# Sheet_1_2025-02-08.net
KiCad netlist of a schematic drawn in Altium Designer
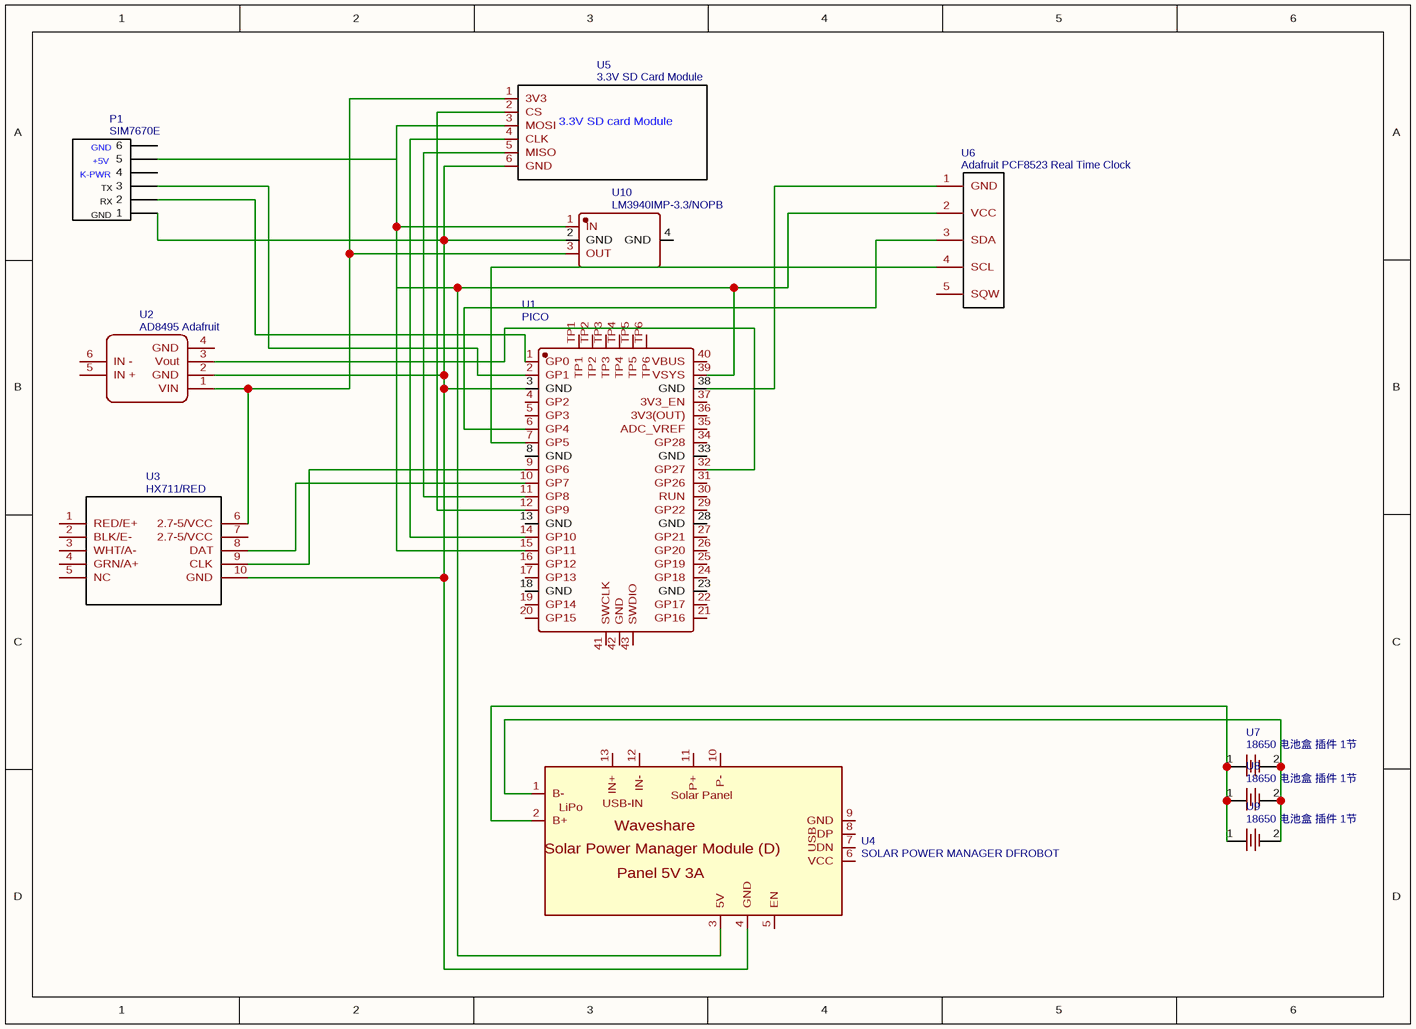
[diagram p0: Sheet_1_2025-02-08.schdoc]

(export (version "E")
  (design (tool "Eeschema 10.0.6"))
  (components
    (comp (ref "P1")
      (value "SIM7670E")
      (fields
        (field (name "MANUFACTURER") "LCSC")
        (field (name "MANUFACTURER PART") "Header-Male-2.54_1x6")
        (field (name "CONTRIBUTOR") "mrilic66")
      )
      (libsource (lib "altium-import") (part "root_2_SIM7670E_"))
    )
    (comp (ref "U1")
      (value "PICO")
      (fields (field (name "MANUFACTURER") "Raspberry Pi(树莓派)") (field (name "CONTRIBUTOR") "lcsc"))
      (libsource (lib "altium-import") (part "root_0_PICO_"))
    )
    (comp (ref "U2")
      (value "AD8495 Adafruit")
      (fields
        (field (name "MANUFACTURER") "Adafruit")
        (field (name "MANUFACTURER PART") "1778")
        (field (name "CONTRIBUTOR") "ralph.v.montfort")
      )
      (libsource (lib "altium-import") (part "root_2_AD8495 Adafruit_"))
    )
    (comp (ref "U3")
      (value "HX711/RED")
      (fields (field (name "CONTRIBUTOR") "lwmd92"))
      (libsource (lib "altium-import") (part "root_0_HX711/RED_"))
    )
    (comp (ref "U4")
      (value "SOLAR POWER MANAGER DFROBOT")
      (fields (field (name "MANUFACTURER") "Sunflower") (field (name "CONTRIBUTOR") "ManarAlkammessy1"))
      (libsource (lib "altium-import") (part "root_0_SOLAR POWER MANAGER DFROBOT_"))
    )
    (comp (ref "U5")
      (value "3.3V SD Card Module")
      (fields (field (name "CONTRIBUTOR") "sumeda91"))
      (libsource (lib "altium-import") (part "root_0_3.3V SD Card Module_"))
    )
    (comp (ref "U6")
      (value "Adafruit PCF8523 Real Time Clock")
      (fields (field (name "CONTRIBUTOR") "Israrengineering"))
      (libsource (lib "altium-import") (part "root_2_Adafruit PCF8523 Real Time Clock_"))
    )
    (comp (ref "U7")
      (value "18650 电池盒 插件 1节")
      (fields (field (name "CONTRIBUTOR") "LCSC"))
      (libsource (lib "altium-import") (part "root_0_18650 电池盒 插件 1节_"))
    )
    (comp (ref "U8")
      (value "18650 电池盒 插件 1节")
      (fields (field (name "CONTRIBUTOR") "LCSC"))
      (libsource (lib "altium-import") (part "root_0_18650 电池盒 插件 1节_"))
    )
    (comp (ref "U9")
      (value "18650 电池盒 插件 1节")
      (fields (field (name "CONTRIBUTOR") "LCSC"))
      (libsource (lib "altium-import") (part "root_0_18650 电池盒 插件 1节_"))
    )
    (comp (ref "U10")
      (value "LM3940IMP-3.3/NOPB")
      (fields (field (name "MANUFACTURER") "TI(德州仪器)") (field (name "CONTRIBUTOR") "LCSC"))
      (libsource (lib "altium-import") (part "root_0_LM3940IMP-3.3/NOPB_"))
    )
  )
  (nets
    (net (code "1") (name "Net-(U1-GP0)") (class "Default")
      (node (ref "P1") (pin "2") (pinfunction "2_2") (pintype "passive"))
      (node (ref "U1") (pin "1") (pinfunction "GP0_1") (pintype "passive"))
    )
    (net (code "2") (name "Net-(U1-GP1)") (class "Default")
      (node (ref "P1") (pin "3") (pinfunction "3_3") (pintype "passive"))
      (node (ref "U1") (pin "2") (pinfunction "GP1_2") (pintype "passive"))
    )
    (net (code "3") (name "Net-(U1-GP4)") (class "Default")
      (node (ref "U1") (pin "6") (pinfunction "GP4_6") (pintype "passive"))
      (node (ref "U6") (pin "3") (pinfunction "SDA_3") (pintype "passive"))
    )
    (net (code "4") (name "Net-(U1-GP5)") (class "Default")
      (node (ref "U1") (pin "7") (pinfunction "GP5_7") (pintype "passive"))
      (node (ref "U6") (pin "4") (pinfunction "SCL_4") (pintype "passive"))
    )
    (net (code "5") (name "Net-(U1-GP6)") (class "Default")
      (node (ref "U1") (pin "9") (pinfunction "GP6_9") (pintype "passive"))
      (node (ref "U3") (pin "9") (pinfunction "CLK_9") (pintype "passive"))
    )
    (net (code "6") (name "Net-(U1-GP7)") (class "Default")
      (node (ref "U1") (pin "10") (pinfunction "GP7_10") (pintype "passive"))
      (node (ref "U3") (pin "8") (pinfunction "DAT_8") (pintype "passive"))
    )
    (net (code "7") (name "Net-(U1-GP8)") (class "Default")
      (node (ref "U1") (pin "11") (pinfunction "GP8_11") (pintype "passive"))
      (node (ref "U5") (pin "5") (pinfunction "MISO_5") (pintype "passive"))
    )
    (net (code "8") (name "Net-(U1-GP9)") (class "Default")
      (node (ref "U1") (pin "12") (pinfunction "GP9_12") (pintype "passive"))
      (node (ref "U5") (pin "2") (pinfunction "CS_2") (pintype "passive"))
    )
    (net (code "9") (name "Net-(U1-GP10)") (class "Default")
      (node (ref "U1") (pin "14") (pinfunction "GP10_14") (pintype "passive"))
      (node (ref "U5") (pin "4") (pinfunction "CLK_4") (pintype "passive"))
    )
    (net (code "10") (name "Net-(U1-GP11)") (class "Default")
      (node (ref "P1") (pin "5") (pinfunction "5_5") (pintype "passive"))
      (node (ref "U1") (pin "15") (pinfunction "GP11_15") (pintype "passive"))
      (node (ref "U1") (pin "39") (pinfunction "VSYS_39") (pintype "passive"))
      (node (ref "U10") (pin "1") (pinfunction "IN_1") (pintype "passive"))
      (node (ref "U4") (pin "3") (pinfunction "5V_3") (pintype "passive"))
      (node (ref "U5") (pin "3") (pinfunction "MOSI_3") (pintype "passive"))
      (node (ref "U6") (pin "2") (pinfunction "VCC_2") (pintype "passive"))
    )
    (net (code "11") (name "Net-(U1-GP27)") (class "Default")
      (node (ref "U1") (pin "32") (pinfunction "GP27_32") (pintype "passive"))
      (node (ref "U2") (pin "3") (pinfunction "Vout_3") (pintype "passive"))
    )
    (net (code "12") (name "Net-(U3-GND)") (class "Default")
      (node (ref "P1") (pin "1") (pinfunction "1_1") (pintype "passive"))
      (node (ref "U1") (pin "3") (pinfunction "GND_3") (pintype "passive"))
      (node (ref "U10") (pin "2") (pinfunction "GND_2") (pintype "passive"))
      (node (ref "U2") (pin "2") (pinfunction "GND_2") (pintype "passive"))
      (node (ref "U3") (pin "10") (pinfunction "GND_10") (pintype "passive"))
      (node (ref "U4") (pin "4") (pinfunction "GND_4") (pintype "passive"))
      (node (ref "U5") (pin "6") (pinfunction "GND_6") (pintype "passive"))
    )
    (net (code "13") (name "Net-(U4-B+)") (class "Default")
      (node (ref "U4") (pin "2") (pinfunction "B+_2") (pintype "passive"))
      (node (ref "U7") (pin "1") (pinfunction "1_1") (pintype "passive"))
      (node (ref "U8") (pin "1") (pinfunction "1_1") (pintype "passive"))
      (node (ref "U9") (pin "1") (pinfunction "1_1") (pintype "passive"))
    )
    (net (code "14") (name "Net-(U4-B-)") (class "Default")
      (node (ref "U4") (pin "1") (pinfunction "B-_1") (pintype "passive"))
      (node (ref "U7") (pin "2") (pinfunction "2_2") (pintype "passive"))
      (node (ref "U8") (pin "2") (pinfunction "2_2") (pintype "passive"))
      (node (ref "U9") (pin "2") (pinfunction "2_2") (pintype "passive"))
    )
    (net (code "15") (name "Net-(U6-GND)") (class "Default")
      (node (ref "U1") (pin "38") (pinfunction "GND_38") (pintype "passive"))
      (node (ref "U6") (pin "1") (pinfunction "GND_1") (pintype "passive"))
    )
    (net (code "16") (name "Net-(U10-OUT)") (class "Default")
      (node (ref "U10") (pin "3") (pinfunction "OUT_3") (pintype "passive"))
      (node (ref "U2") (pin "1") (pinfunction "VIN_1") (pintype "passive"))
      (node (ref "U3") (pin "6") (pinfunction "2.7-5/VCC_6") (pintype "passive"))
      (node (ref "U5") (pin "1") (pinfunction "3V3_1") (pintype "passive"))
    )
    (net (code "17") (name "unconnected-(P1-Pad4)") (class "Default")
      (node (ref "P1") (pin "4") (pinfunction "4_4") (pintype "passive"))
    )
    (net (code "18") (name "unconnected-(P1-Pad6)") (class "Default")
      (node (ref "P1") (pin "6") (pinfunction "6_6") (pintype "passive"))
    )
    (net (code "19") (name "unconnected-(U1-3V3(OUT)-Pad36)") (class "Default")
      (node (ref "U1") (pin "36") (pinfunction "3V3(OUT)_36") (pintype "passive"))
    )
    (net (code "20") (name "unconnected-(U1-3V3_EN-Pad37)") (class "Default")
      (node (ref "U1") (pin "37") (pinfunction "3V3_EN_37") (pintype "passive"))
    )
    (net (code "21") (name "unconnected-(U1-ADC_VREF-Pad35)") (class "Default")
      (node (ref "U1") (pin "35") (pinfunction "ADC_VREF_35") (pintype "passive"))
    )
    (net (code "22") (name "unconnected-(U1-GND-Pad8)") (class "Default")
      (node (ref "U1") (pin "8") (pinfunction "GND_8") (pintype "passive"))
    )
    (net (code "23") (name "unconnected-(U1-GND-Pad13)") (class "Default")
      (node (ref "U1") (pin "13") (pinfunction "GND_13") (pintype "passive"))
    )
    (net (code "24") (name "unconnected-(U1-GND-Pad18)") (class "Default")
      (node (ref "U1") (pin "18") (pinfunction "GND_18") (pintype "passive"))
    )
    (net (code "25") (name "unconnected-(U1-GND-Pad23)") (class "Default")
      (node (ref "U1") (pin "23") (pinfunction "GND_23") (pintype "passive"))
    )
    (net (code "26") (name "unconnected-(U1-GND-Pad28)") (class "Default")
      (node (ref "U1") (pin "28") (pinfunction "GND_28") (pintype "passive"))
    )
    (net (code "27") (name "unconnected-(U1-GND-Pad33)") (class "Default")
      (node (ref "U1") (pin "33") (pinfunction "GND_33") (pintype "passive"))
    )
    (net (code "28") (name "unconnected-(U1-GND-Pad42)") (class "Default")
      (node (ref "U1") (pin "42") (pinfunction "GND_42") (pintype "passive"))
    )
    (net (code "29") (name "unconnected-(U1-GP2-Pad4)") (class "Default")
      (node (ref "U1") (pin "4") (pinfunction "GP2_4") (pintype "passive"))
    )
    (net (code "30") (name "unconnected-(U1-GP3-Pad5)") (class "Default")
      (node (ref "U1") (pin "5") (pinfunction "GP3_5") (pintype "passive"))
    )
    (net (code "31") (name "unconnected-(U1-GP12-Pad16)") (class "Default")
      (node (ref "U1") (pin "16") (pinfunction "GP12_16") (pintype "passive"))
    )
    (net (code "32") (name "unconnected-(U1-GP13-Pad17)") (class "Default")
      (node (ref "U1") (pin "17") (pinfunction "GP13_17") (pintype "passive"))
    )
    (net (code "33") (name "unconnected-(U1-GP14-Pad19)") (class "Default")
      (node (ref "U1") (pin "19") (pinfunction "GP14_19") (pintype "passive"))
    )
    (net (code "34") (name "unconnected-(U1-GP15-Pad20)") (class "Default")
      (node (ref "U1") (pin "20") (pinfunction "GP15_20") (pintype "passive"))
    )
    (net (code "35") (name "unconnected-(U1-GP16-Pad21)") (class "Default")
      (node (ref "U1") (pin "21") (pinfunction "GP16_21") (pintype "passive"))
    )
    (net (code "36") (name "unconnected-(U1-GP17-Pad22)") (class "Default")
      (node (ref "U1") (pin "22") (pinfunction "GP17_22") (pintype "passive"))
    )
    (net (code "37") (name "unconnected-(U1-GP18-Pad24)") (class "Default")
      (node (ref "U1") (pin "24") (pinfunction "GP18_24") (pintype "passive"))
    )
    (net (code "38") (name "unconnected-(U1-GP19-Pad25)") (class "Default")
      (node (ref "U1") (pin "25") (pinfunction "GP19_25") (pintype "passive"))
    )
    (net (code "39") (name "unconnected-(U1-GP20-Pad26)") (class "Default")
      (node (ref "U1") (pin "26") (pinfunction "GP20_26") (pintype "passive"))
    )
    (net (code "40") (name "unconnected-(U1-GP21-Pad27)") (class "Default")
      (node (ref "U1") (pin "27") (pinfunction "GP21_27") (pintype "passive"))
    )
    (net (code "41") (name "unconnected-(U1-GP22-Pad29)") (class "Default")
      (node (ref "U1") (pin "29") (pinfunction "GP22_29") (pintype "passive"))
    )
    (net (code "42") (name "unconnected-(U1-GP26-Pad31)") (class "Default")
      (node (ref "U1") (pin "31") (pinfunction "GP26_31") (pintype "passive"))
    )
    (net (code "43") (name "unconnected-(U1-GP28-Pad34)") (class "Default")
      (node (ref "U1") (pin "34") (pinfunction "GP28_34") (pintype "passive"))
    )
    (net (code "44") (name "unconnected-(U1-PadTP1)") (class "Default")
      (node (ref "U1") (pin "TP1") (pinfunction "TP1_TP1") (pintype "passive"))
    )
    (net (code "45") (name "unconnected-(U1-PadTP2)") (class "Default")
      (node (ref "U1") (pin "TP2") (pinfunction "TP2_TP2") (pintype "passive"))
    )
    (net (code "46") (name "unconnected-(U1-PadTP3)") (class "Default")
      (node (ref "U1") (pin "TP3") (pinfunction "TP3_TP3") (pintype "passive"))
    )
    (net (code "47") (name "unconnected-(U1-PadTP4)") (class "Default")
      (node (ref "U1") (pin "TP4") (pinfunction "TP4_TP4") (pintype "passive"))
    )
    (net (code "48") (name "unconnected-(U1-PadTP5)") (class "Default")
      (node (ref "U1") (pin "TP5") (pinfunction "TP5_TP5") (pintype "passive"))
    )
    (net (code "49") (name "unconnected-(U1-PadTP6)") (class "Default")
      (node (ref "U1") (pin "TP6") (pinfunction "TP6_TP6") (pintype "passive"))
    )
    (net (code "50") (name "unconnected-(U1-RUN-Pad30)") (class "Default")
      (node (ref "U1") (pin "30") (pinfunction "RUN_30") (pintype "passive"))
    )
    (net (code "51") (name "unconnected-(U1-SWCLK-Pad41)") (class "Default")
      (node (ref "U1") (pin "41") (pinfunction "SWCLK_41") (pintype "passive"))
    )
    (net (code "52") (name "unconnected-(U1-SWDIO-Pad43)") (class "Default")
      (node (ref "U1") (pin "43") (pinfunction "SWDIO_43") (pintype "passive"))
    )
    (net (code "53") (name "unconnected-(U1-VBUS-Pad40)") (class "Default")
      (node (ref "U1") (pin "40") (pinfunction "VBUS_40") (pintype "passive"))
    )
    (net (code "54") (name "unconnected-(U2-GND-Pad4)") (class "Default")
      (node (ref "U2") (pin "4") (pinfunction "GND_4") (pintype "passive"))
    )
    (net (code "55") (name "unconnected-(U2-IN_+-Pad5)") (class "Default")
      (node (ref "U2") (pin "5") (pinfunction "IN_+_5") (pintype "passive"))
    )
    (net (code "56") (name "unconnected-(U2-IN_--Pad6)") (class "Default")
      (node (ref "U2") (pin "6") (pinfunction "IN_-_6") (pintype "passive"))
    )
    (net (code "57") (name "unconnected-(U3-2.7-5{slash}VCC-Pad7)") (class "Default")
      (node (ref "U3") (pin "7") (pinfunction "2.7-5/VCC_7") (pintype "passive"))
    )
    (net (code "58") (name "unconnected-(U3-BLK{slash}E--Pad2)") (class "Default")
      (node (ref "U3") (pin "2") (pinfunction "BLK/E-_2") (pintype "passive"))
    )
    (net (code "59") (name "unconnected-(U3-GRN{slash}A+-Pad4)") (class "Default")
      (node (ref "U3") (pin "4") (pinfunction "GRN/A+_4") (pintype "passive"))
    )
    (net (code "60") (name "unconnected-(U3-NC-Pad5)") (class "Default")
      (node (ref "U3") (pin "5") (pinfunction "NC_5") (pintype "passive"))
    )
    (net (code "61") (name "unconnected-(U3-RED{slash}E+-Pad1)") (class "Default")
      (node (ref "U3") (pin "1") (pinfunction "RED/E+_1") (pintype "passive"))
    )
    (net (code "62") (name "unconnected-(U3-WHT{slash}A--Pad3)") (class "Default")
      (node (ref "U3") (pin "3") (pinfunction "WHT/A-_3") (pintype "passive"))
    )
    (net (code "63") (name "unconnected-(U4-DN-Pad7)") (class "Default")
      (node (ref "U4") (pin "7") (pinfunction "DN_7") (pintype "passive"))
    )
    (net (code "64") (name "unconnected-(U4-DP-Pad8)") (class "Default")
      (node (ref "U4") (pin "8") (pinfunction "DP_8") (pintype "passive"))
    )
    (net (code "65") (name "unconnected-(U4-EN-Pad5)") (class "Default")
      (node (ref "U4") (pin "5") (pinfunction "EN_5") (pintype "passive"))
    )
    (net (code "66") (name "unconnected-(U4-GND-Pad9)") (class "Default")
      (node (ref "U4") (pin "9") (pinfunction "GND_9") (pintype "passive"))
    )
    (net (code "67") (name "unconnected-(U4-IN+-Pad13)") (class "Default")
      (node (ref "U4") (pin "13") (pinfunction "IN+_13") (pintype "passive"))
    )
    (net (code "68") (name "unconnected-(U4-IN--Pad12)") (class "Default")
      (node (ref "U4") (pin "12") (pinfunction "IN-_12") (pintype "passive"))
    )
    (net (code "69") (name "unconnected-(U4-P+-Pad11)") (class "Default")
      (node (ref "U4") (pin "11") (pinfunction "P+_11") (pintype "passive"))
    )
    (net (code "70") (name "unconnected-(U4-P--Pad10)") (class "Default")
      (node (ref "U4") (pin "10") (pinfunction "P-_10") (pintype "passive"))
    )
    (net (code "71") (name "unconnected-(U4-VCC-Pad6)") (class "Default")
      (node (ref "U4") (pin "6") (pinfunction "VCC_6") (pintype "passive"))
    )
    (net (code "72") (name "unconnected-(U6-SQW-Pad5)") (class "Default")
      (node (ref "U6") (pin "5") (pinfunction "SQW_5") (pintype "passive"))
    )
    (net (code "73") (name "unconnected-(U10-GND-Pad4)") (class "Default")
      (node (ref "U10") (pin "4") (pinfunction "GND_4") (pintype "passive"))
    )
  )
)
